# top.net
KiCad netlist of a schematic drawn in Altium Designer
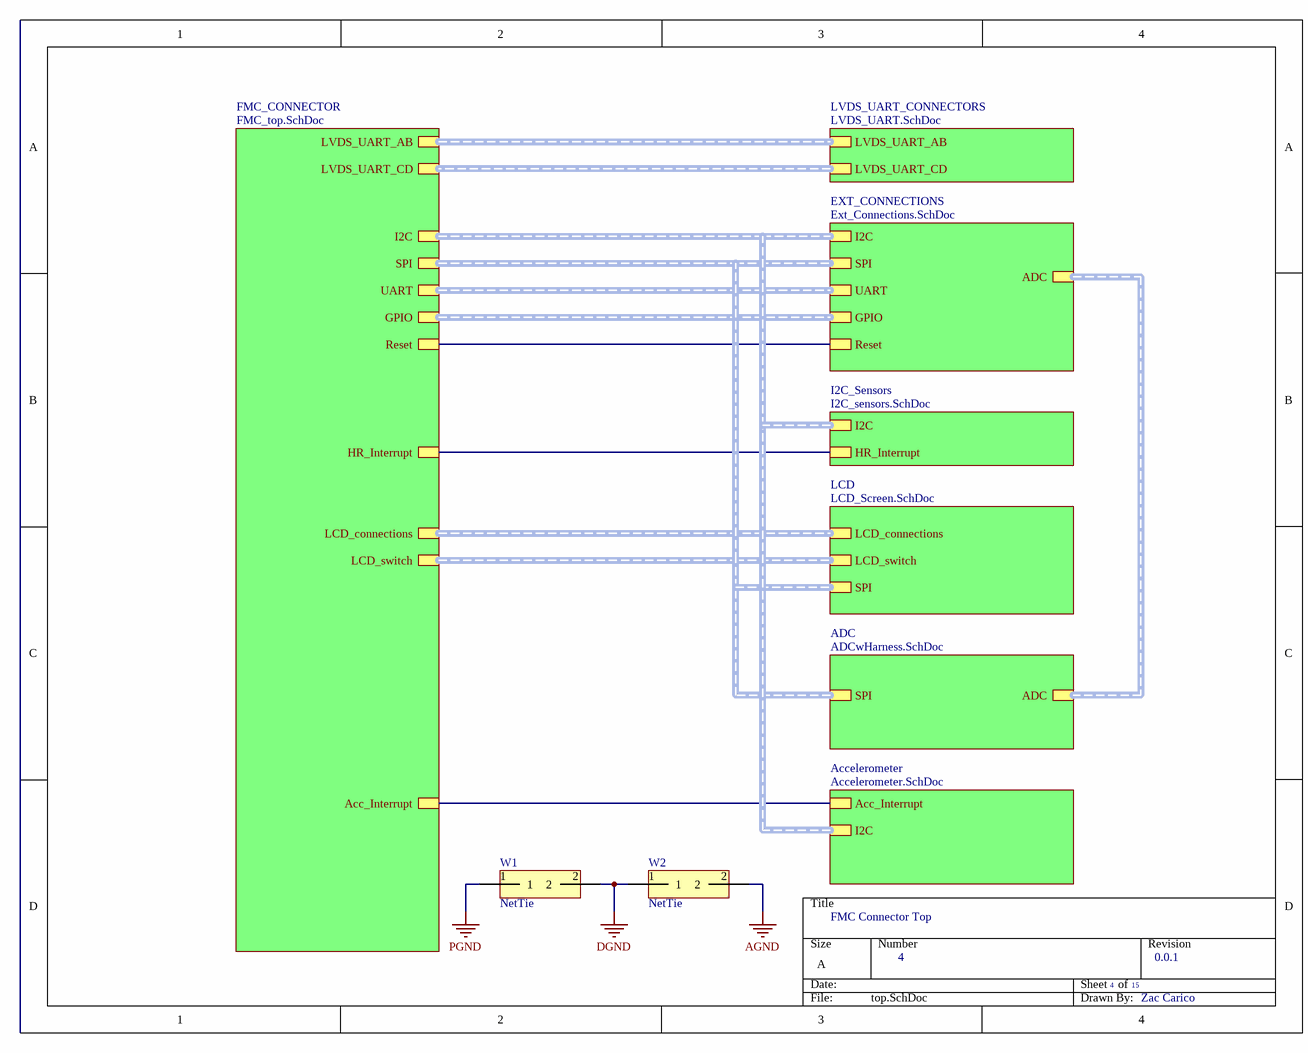
[diagram p0: top.SchDoc]

(export (version "E")
  (design (tool "Eeschema 10.0.6"))
  (components
    (comp (ref "W1") (value "NetTie") (footprint "NetTie") (libsource (lib "Components") (part "NetTie")))
    (comp (ref "W2") (value "NetTie") (footprint "NetTie") (libsource (lib "Components") (part "NetTie")))
  )
  (nets
    (net (code "12") (name "AGND") (class "Default")
      (node (ref "W2") (pin "2") (pinfunction "2_2") (pintype "passive"))
    )
    (net (code "13") (name "DGND") (class "Default")
      (node (ref "W1") (pin "2") (pinfunction "2_2") (pintype "passive"))
      (node (ref "W2") (pin "1") (pinfunction "1_1") (pintype "passive"))
    )
    (net (code "14") (name "PGND") (class "Default")
      (node (ref "W1") (pin "1") (pinfunction "1_1") (pintype "passive"))
    )
  )
)
